# Sheet1.net
KiCad netlist of a schematic drawn in Altium Designer
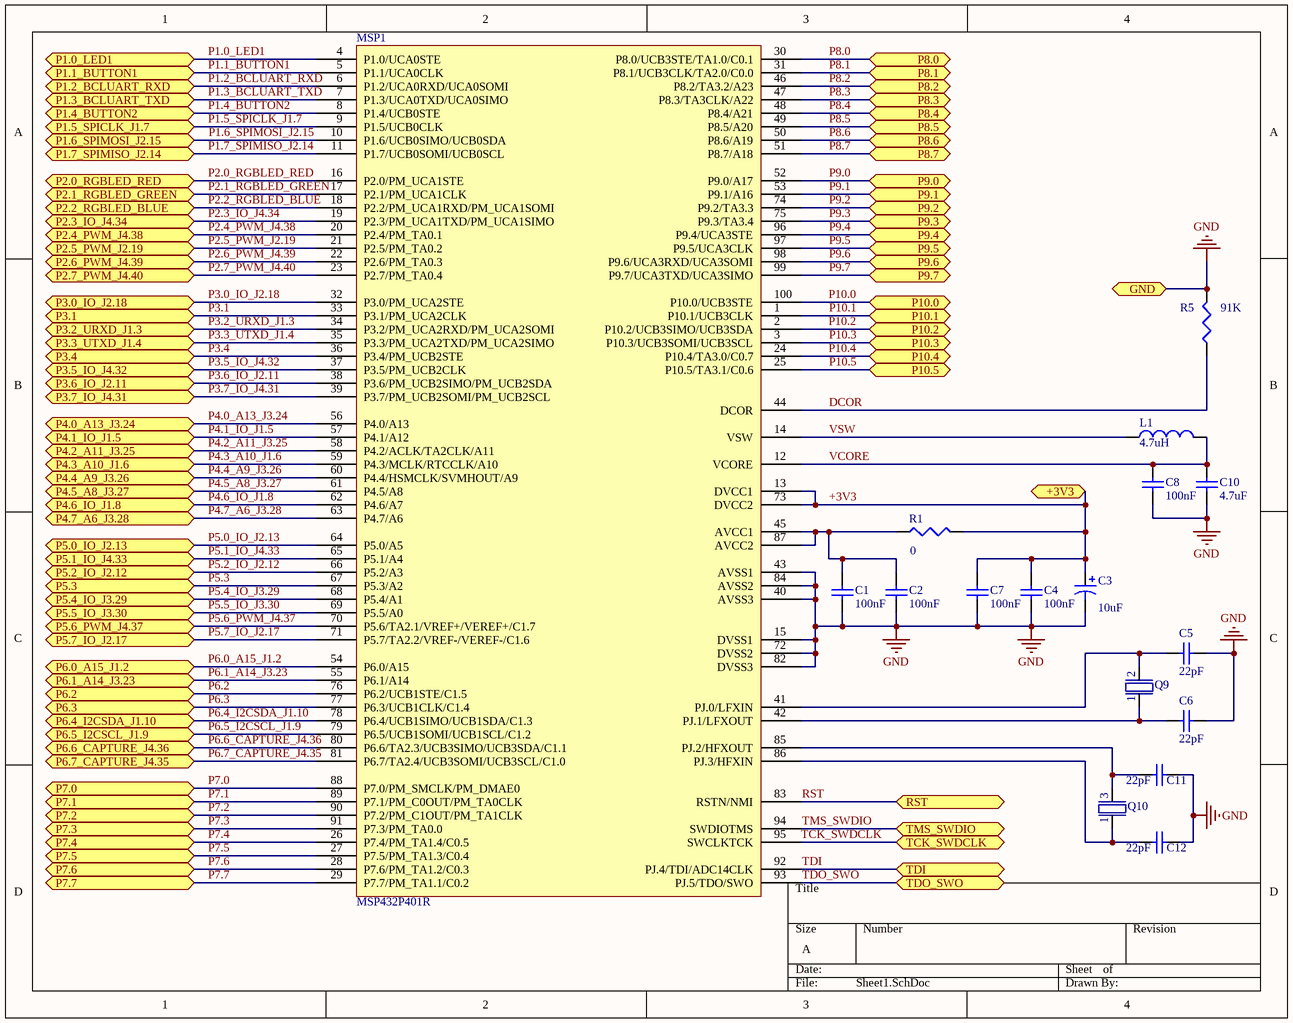
[diagram p0: Sheet1.SchDoc]

(export (version "E")
  (design (tool "Eeschema 10.0.6"))
  (components
    (comp (ref "C1")
      (value "100nF")
      (footprint "0402")
      (description "Capacitor (Semiconductor SIM Model)")
      (fields (field (name "Comment") "Cap Semi") (field (name "PUBLISHER") "Altium Limited"))
      (libsource (lib "Miscellaneous Devices") (part "Cap Semi"))
    )
    (comp (ref "C2")
      (value "100nF")
      (footprint "0402")
      (description "Capacitor (Semiconductor SIM Model)")
      (fields (field (name "Comment") "Cap Semi") (field (name "PUBLISHER") "Altium Limited"))
      (libsource (lib "Miscellaneous Devices") (part "Cap Semi"))
    )
    (comp (ref "C3")
      (value "10uF")
      (footprint "C0805")
      (description "Polarized Capacitor (Surface Mount)")
      (fields (field (name "Comment") "Cap Pol3") (field (name "PUBLISHER") "Altium Limited"))
      (libsource (lib "Miscellaneous Devices") (part "Cap Pol3"))
    )
    (comp (ref "C4")
      (value "100nF")
      (footprint "0402")
      (description "Capacitor (Semiconductor SIM Model)")
      (fields (field (name "Comment") "Cap Semi") (field (name "PUBLISHER") "Altium Limited"))
      (libsource (lib "Miscellaneous Devices") (part "Cap Semi"))
    )
    (comp (ref "C5")
      (value "22pF")
      (footprint "0402")
      (description "Capacitor (Semiconductor SIM Model)")
      (fields (field (name "Comment") "Cap Semi") (field (name "PUBLISHER") "Altium Limited"))
      (libsource (lib "Miscellaneous Devices") (part "Cap Semi"))
    )
    (comp (ref "C6")
      (value "22pF")
      (footprint "0402")
      (description "Capacitor (Semiconductor SIM Model)")
      (fields (field (name "Comment") "Cap Semi") (field (name "PUBLISHER") "Altium Limited"))
      (libsource (lib "Miscellaneous Devices") (part "Cap Semi"))
    )
    (comp (ref "C7")
      (value "100nF")
      (footprint "0402")
      (description "Capacitor (Semiconductor SIM Model)")
      (fields (field (name "Comment") "Cap Semi") (field (name "PUBLISHER") "Altium Limited"))
      (libsource (lib "Miscellaneous Devices") (part "Cap Semi"))
    )
    (comp (ref "C8")
      (value "100nF")
      (footprint "0402")
      (description "Capacitor (Semiconductor SIM Model)")
      (fields (field (name "Comment") "Cap Semi") (field (name "PUBLISHER") "Altium Limited"))
      (libsource (lib "Miscellaneous Devices") (part "Cap Semi"))
    )
    (comp (ref "C10")
      (value "4.7uF")
      (footprint "0402")
      (description "Capacitor (Semiconductor SIM Model)")
      (fields (field (name "Comment") "Cap Semi") (field (name "PUBLISHER") "Altium Limited"))
      (libsource (lib "Miscellaneous Devices") (part "Cap Semi"))
    )
    (comp (ref "C11")
      (value "22pF")
      (footprint "0402")
      (description "Capacitor (Semiconductor SIM Model)")
      (fields (field (name "Comment") "Cap Semi") (field (name "PUBLISHER") "Altium Limited"))
      (libsource (lib "Miscellaneous Devices") (part "Cap Semi"))
    )
    (comp (ref "C12")
      (value "22pF")
      (footprint "0402")
      (description "Capacitor (Semiconductor SIM Model)")
      (fields (field (name "Comment") "Cap Semi") (field (name "PUBLISHER") "Altium Limited"))
      (libsource (lib "Miscellaneous Devices") (part "Cap Semi"))
    )
    (comp (ref "L1")
      (value "4.7uH")
      (footprint "0402-A")
      (description "Inductor")
      (fields (field (name "PUBLISHER") "Altium Limited"))
      (libsource (lib "Miscellaneous Devices") (part "Inductor"))
    )
    (comp (ref "MSP1")
      (value "MSP432P401R")
      (footprint "MSP432P401R")
      (libsource (lib "actuatorBoard") (part "MSP432P401R"))
    )
    (comp (ref "Q9")
      (value "Crystal Oscillator")
      (fields (field (name "PIN1") "1") (field (name "PIN2") "2"))
      (libsource (lib "actuatorBoard") (part "Crystal Oscillator"))
    )
    (comp (ref "Q10")
      (value "Crystal Oscillator")
      (fields (field (name "PIN1") "1") (field (name "PIN2") "3"))
      (libsource (lib "actuatorBoard") (part "Crystal Oscillator"))
    )
    (comp (ref "R1")
      (value "0")
      (footprint "J1-0603")
      (description "Resistor")
      (fields (field (name "Comment") "Res3") (field (name "PUBLISHER") "Altium Limited"))
      (libsource (lib "Miscellaneous Devices") (part "Res3"))
    )
    (comp (ref "R5")
      (value "91K")
      (footprint "J1-0603")
      (description "Resistor")
      (fields (field (name "Comment") "Res3") (field (name "PUBLISHER") "Altium Limited"))
      (libsource (lib "Miscellaneous Devices") (part "Res3"))
    )
  )
  (nets
    (net (code "1") (name "/+3V3") (class "Default")
      (node (ref "C3") (pin "1") (pinfunction "1_1") (pintype "passive"))
      (node (ref "C4") (pin "2") (pinfunction "2_2") (pintype "passive"))
      (node (ref "C7") (pin "2") (pinfunction "2_2") (pintype "passive"))
      (node (ref "MSP1") (pin "13") (pinfunction "DVCC1_13") (pintype "passive"))
      (node (ref "MSP1") (pin "73") (pinfunction "DVCC2_73") (pintype "passive"))
      (node (ref "R1") (pin "2") (pinfunction "2_2") (pintype "passive"))
    )
    (net (code "2") (name "/DCOR") (class "Default")
      (node (ref "MSP1") (pin "44") (pinfunction "DCOR_44") (pintype "passive"))
      (node (ref "R5") (pin "1") (pinfunction "1_1") (pintype "passive"))
    )
    (net (code "3") (name "/P1.0_LED1") (class "Default")
      (node (ref "MSP1") (pin "4") (pinfunction "P1.0/UCA0STE_4") (pintype "passive"))
    )
    (net (code "4") (name "/P1.1_BUTTON1") (class "Default")
      (node (ref "MSP1") (pin "5") (pinfunction "P1.1/UCA0CLK_5") (pintype "passive"))
    )
    (net (code "5") (name "/P1.2_BCLUART_RXD") (class "Default")
      (node (ref "MSP1") (pin "6") (pinfunction "P1.2/UCA0RXD/UCA0SOMI_6") (pintype "passive"))
    )
    (net (code "6") (name "/P1.3_BCLUART_TXD") (class "Default")
      (node (ref "MSP1") (pin "7") (pinfunction "P1.3/UCA0TXD/UCA0SIMO_7") (pintype "passive"))
    )
    (net (code "7") (name "/P1.4_BUTTON2") (class "Default")
      (node (ref "MSP1") (pin "8") (pinfunction "P1.4/UCB0STE_8") (pintype "passive"))
    )
    (net (code "8") (name "/P1.5_SPICLK_J1.7") (class "Default")
      (node (ref "MSP1") (pin "9") (pinfunction "P1.5/UCB0CLK_9") (pintype "passive"))
    )
    (net (code "9") (name "/P1.6_SPIMOSI_J2.15") (class "Default")
      (node (ref "MSP1") (pin "10") (pinfunction "P1.6/UCB0SIMO/UCB0SDA_10") (pintype "passive"))
    )
    (net (code "10") (name "/P1.7_SPIMISO_J2.14") (class "Default")
      (node (ref "MSP1") (pin "11") (pinfunction "P1.7/UCB0SOMI/UCB0SCL_11") (pintype "passive"))
    )
    (net (code "11") (name "/P2.0_RGBLED_RED") (class "Default")
      (node (ref "MSP1") (pin "16") (pinfunction "P2.0/PM_UCA1STE_16") (pintype "passive"))
    )
    (net (code "12") (name "/P2.1_RGBLED_GREEN") (class "Default")
      (node (ref "MSP1") (pin "17") (pinfunction "P2.1/PM_UCA1CLK_17") (pintype "passive"))
    )
    (net (code "13") (name "/P2.2_RGBLED_BLUE") (class "Default")
      (node (ref "MSP1") (pin "18") (pinfunction "P2.2/PM_UCA1RXD/PM_UCA1SOMI_18") (pintype "passive"))
    )
    (net (code "14") (name "/P2.3_IO_J4.34") (class "Default")
      (node (ref "MSP1") (pin "19") (pinfunction "P2.3/PM_UCA1TXD/PM_UCA1SIMO_19") (pintype "passive"))
    )
    (net (code "15") (name "/P2.4_PWM_J4.38") (class "Default")
      (node (ref "MSP1") (pin "20") (pinfunction "P2.4/PM_TA0.1_20") (pintype "passive"))
    )
    (net (code "16") (name "/P2.5_PWM_J2.19") (class "Default")
      (node (ref "MSP1") (pin "21") (pinfunction "P2.5/PM_TA0.2_21") (pintype "passive"))
    )
    (net (code "17") (name "/P2.6_PWM_J4.39") (class "Default")
      (node (ref "MSP1") (pin "22") (pinfunction "P2.6/PM_TA0.3_22") (pintype "passive"))
    )
    (net (code "18") (name "/P2.7_PWM_J4.40") (class "Default")
      (node (ref "MSP1") (pin "23") (pinfunction "P2.7/PM_TA0.4_23") (pintype "passive"))
    )
    (net (code "19") (name "/P3.0_IO_J2.18") (class "Default")
      (node (ref "MSP1") (pin "32") (pinfunction "P3.0/PM_UCA2STE_32") (pintype "passive"))
    )
    (net (code "20") (name "/P3.1") (class "Default")
      (node (ref "MSP1") (pin "33") (pinfunction "P3.1/PM_UCA2CLK_33") (pintype "passive"))
    )
    (net (code "21") (name "/P3.2_URXD_J1.3") (class "Default")
      (node (ref "MSP1") (pin "34") (pinfunction "P3.2/PM_UCA2RXD/PM_UCA2SOMI_34") (pintype "passive"))
    )
    (net (code "22") (name "/P3.3_UTXD_J1.4") (class "Default")
      (node (ref "MSP1") (pin "35") (pinfunction "P3.3/PM_UCA2TXD/PM_UCA2SIMO_35") (pintype "passive"))
    )
    (net (code "23") (name "/P3.4") (class "Default")
      (node (ref "MSP1") (pin "36") (pinfunction "P3.4/PM_UCB2STE_36") (pintype "passive"))
    )
    (net (code "24") (name "/P3.5_IO_J4.32") (class "Default")
      (node (ref "MSP1") (pin "37") (pinfunction "P3.5/PM_UCB2CLK_37") (pintype "passive"))
    )
    (net (code "25") (name "/P3.6_IO_J2.11") (class "Default")
      (node (ref "MSP1") (pin "38") (pinfunction "P3.6/PM_UCB2SIMO/PM_UCB2SDA_38") (pintype "passive"))
    )
    (net (code "26") (name "/P3.7_IO_J4.31") (class "Default")
      (node (ref "MSP1") (pin "39") (pinfunction "P3.7/PM_UCB2SOMI/PM_UCB2SCL_39") (pintype "passive"))
    )
    (net (code "27") (name "/P4.0_A13_J3.24") (class "Default")
      (node (ref "MSP1") (pin "56") (pinfunction "P4.0/A13_56") (pintype "passive"))
    )
    (net (code "28") (name "/P4.1_IO_J1.5") (class "Default")
      (node (ref "MSP1") (pin "57") (pinfunction "P4.1/A12_57") (pintype "passive"))
    )
    (net (code "29") (name "/P4.2_A11_J3.25") (class "Default")
      (node (ref "MSP1") (pin "58") (pinfunction "P4.2/ACLK/TA2CLK/A11_58") (pintype "passive"))
    )
    (net (code "30") (name "/P4.3_A10_J1.6") (class "Default")
      (node (ref "MSP1") (pin "59") (pinfunction "P4.3/MCLK/RTCCLK/A10_59") (pintype "passive"))
    )
    (net (code "31") (name "/P4.4_A9_J3.26") (class "Default")
      (node (ref "MSP1") (pin "60") (pinfunction "P4.4/HSMCLK/SVMHOUT/A9_60") (pintype "passive"))
    )
    (net (code "32") (name "/P4.5_A8_J3.27") (class "Default")
      (node (ref "MSP1") (pin "61") (pinfunction "P4.5/A8_61") (pintype "passive"))
    )
    (net (code "33") (name "/P4.6_IO_J1.8") (class "Default")
      (node (ref "MSP1") (pin "62") (pinfunction "P4.6/A7_62") (pintype "passive"))
    )
    (net (code "34") (name "/P4.7_A6_J3.28") (class "Default")
      (node (ref "MSP1") (pin "63") (pinfunction "P4.7/A6_63") (pintype "passive"))
    )
    (net (code "35") (name "/P5.0_IO_J2.13") (class "Default")
      (node (ref "MSP1") (pin "64") (pinfunction "P5.0/A5_64") (pintype "passive"))
    )
    (net (code "36") (name "/P5.1_IO_J4.33") (class "Default")
      (node (ref "MSP1") (pin "65") (pinfunction "P5.1/A4_65") (pintype "passive"))
    )
    (net (code "37") (name "/P5.2_IO_J2.12") (class "Default")
      (node (ref "MSP1") (pin "66") (pinfunction "P5.2/A3_66") (pintype "passive"))
    )
    (net (code "38") (name "/P5.3") (class "Default")
      (node (ref "MSP1") (pin "67") (pinfunction "P5.3/A2_67") (pintype "passive"))
    )
    (net (code "39") (name "/P5.4_IO_J3.29") (class "Default")
      (node (ref "MSP1") (pin "68") (pinfunction "P5.4/A1_68") (pintype "passive"))
    )
    (net (code "40") (name "/P5.5_IO_J3.30") (class "Default")
      (node (ref "MSP1") (pin "69") (pinfunction "P5.5/A0_69") (pintype "passive"))
    )
    (net (code "41") (name "/P5.6_PWM_J4.37") (class "Default")
      (node (ref "MSP1") (pin "70") (pinfunction "P5.6/TA2.1/VREF+/VEREF+/C1.7_70") (pintype "passive"))
    )
    (net (code "42") (name "/P5.7_IO_J2.17") (class "Default")
      (node (ref "MSP1") (pin "71") (pinfunction "P5.7/TA2.2/VREF-/VEREF-/C1.6_71") (pintype "passive"))
    )
    (net (code "43") (name "/P6.0_A15_J1.2") (class "Default")
      (node (ref "MSP1") (pin "54") (pinfunction "P6.0/A15_54") (pintype "passive"))
    )
    (net (code "44") (name "/P6.1_A14_J3.23") (class "Default")
      (node (ref "MSP1") (pin "55") (pinfunction "P6.1/A14_55") (pintype "passive"))
    )
    (net (code "45") (name "/P6.2") (class "Default")
      (node (ref "MSP1") (pin "76") (pinfunction "P6.2/UCB1STE/C1.5_76") (pintype "passive"))
    )
    (net (code "46") (name "/P6.3") (class "Default")
      (node (ref "MSP1") (pin "77") (pinfunction "P6.3/UCB1CLK/C1.4_77") (pintype "passive"))
    )
    (net (code "47") (name "/P6.4_I2CSDA_J1.10") (class "Default")
      (node (ref "MSP1") (pin "78") (pinfunction "P6.4/UCB1SIMO/UCB1SDA/C1.3_78") (pintype "passive"))
    )
    (net (code "48") (name "/P6.5_I2CSCL_J1.9") (class "Default")
      (node (ref "MSP1") (pin "79") (pinfunction "P6.5/UCB1SOMI/UCB1SCL/C1.2_79") (pintype "passive"))
    )
    (net (code "49") (name "/P6.6_CAPTURE_J4.36") (class "Default")
      (node (ref "MSP1") (pin "80") (pinfunction "P6.6/TA2.3/UCB3SIMO/UCB3SDA/C1.1_80") (pintype "passive"))
    )
    (net (code "50") (name "/P6.7_CAPTURE_J4.35") (class "Default")
      (node (ref "MSP1") (pin "81") (pinfunction "P6.7/TA2.4/UCB3SOMI/UCB3SCL/C1.0_81") (pintype "passive"))
    )
    (net (code "51") (name "/P7.0") (class "Default")
      (node (ref "MSP1") (pin "88") (pinfunction "P7.0/PM_SMCLK/PM_DMAE0_88") (pintype "passive"))
    )
    (net (code "52") (name "/P7.1") (class "Default")
      (node (ref "MSP1") (pin "89") (pinfunction "P7.1/PM_C0OUT/PM_TA0CLK_89") (pintype "passive"))
    )
    (net (code "53") (name "/P7.2") (class "Default")
      (node (ref "MSP1") (pin "90") (pinfunction "P7.2/PM_C1OUT/PM_TA1CLK_90") (pintype "passive"))
    )
    (net (code "54") (name "/P7.3") (class "Default")
      (node (ref "MSP1") (pin "91") (pinfunction "P7.3/PM_TA0.0_91") (pintype "passive"))
    )
    (net (code "55") (name "/P7.4") (class "Default")
      (node (ref "MSP1") (pin "26") (pinfunction "P7.4/PM_TA1.4/C0.5_26") (pintype "passive"))
    )
    (net (code "56") (name "/P7.5") (class "Default")
      (node (ref "MSP1") (pin "27") (pinfunction "P7.5/PM_TA1.3/C0.4_27") (pintype "passive"))
    )
    (net (code "57") (name "/P7.6") (class "Default")
      (node (ref "MSP1") (pin "28") (pinfunction "P7.6/PM_TA1.2/C0.3_28") (pintype "passive"))
    )
    (net (code "58") (name "/P7.7") (class "Default")
      (node (ref "MSP1") (pin "29") (pinfunction "P7.7/PM_TA1.1/C0.2_29") (pintype "passive"))
    )
    (net (code "59") (name "/P8.0") (class "Default")
      (node (ref "MSP1") (pin "30") (pinfunction "P8.0/UCB3STE/TA1.0/C0.1_30") (pintype "passive"))
    )
    (net (code "60") (name "/P8.1") (class "Default")
      (node (ref "MSP1") (pin "31") (pinfunction "P8.1/UCB3CLK/TA2.0/C0.0_31") (pintype "passive"))
    )
    (net (code "61") (name "/P8.2") (class "Default")
      (node (ref "MSP1") (pin "46") (pinfunction "P8.2/TA3.2/A23_46") (pintype "passive"))
    )
    (net (code "62") (name "/P8.3") (class "Default")
      (node (ref "MSP1") (pin "47") (pinfunction "P8.3/TA3CLK/A22_47") (pintype "passive"))
    )
    (net (code "63") (name "/P8.4") (class "Default")
      (node (ref "MSP1") (pin "48") (pinfunction "P8.4/A21_48") (pintype "passive"))
    )
    (net (code "64") (name "/P8.5") (class "Default")
      (node (ref "MSP1") (pin "49") (pinfunction "P8.5/A20_49") (pintype "passive"))
    )
    (net (code "65") (name "/P8.6") (class "Default")
      (node (ref "MSP1") (pin "50") (pinfunction "P8.6/A19_50") (pintype "passive"))
    )
    (net (code "66") (name "/P8.7") (class "Default")
      (node (ref "MSP1") (pin "51") (pinfunction "P8.7/A18_51") (pintype "passive"))
    )
    (net (code "67") (name "/P9.0") (class "Default")
      (node (ref "MSP1") (pin "52") (pinfunction "P9.0/A17_52") (pintype "passive"))
    )
    (net (code "68") (name "/P9.1") (class "Default")
      (node (ref "MSP1") (pin "53") (pinfunction "P9.1/A16_53") (pintype "passive"))
    )
    (net (code "69") (name "/P9.2") (class "Default")
      (node (ref "MSP1") (pin "74") (pinfunction "P9.2/TA3.3_74") (pintype "passive"))
    )
    (net (code "70") (name "/P9.3") (class "Default")
      (node (ref "MSP1") (pin "75") (pinfunction "P9.3/TA3.4_75") (pintype "passive"))
    )
    (net (code "71") (name "/P9.4") (class "Default")
      (node (ref "MSP1") (pin "96") (pinfunction "P9.4/UCA3STE_96") (pintype "passive"))
    )
    (net (code "72") (name "/P9.5") (class "Default")
      (node (ref "MSP1") (pin "97") (pinfunction "P9.5/UCA3CLK_97") (pintype "passive"))
    )
    (net (code "73") (name "/P9.6") (class "Default")
      (node (ref "MSP1") (pin "98") (pinfunction "P9.6/UCA3RXD/UCA3SOMI_98") (pintype "passive"))
    )
    (net (code "74") (name "/P9.7") (class "Default")
      (node (ref "MSP1") (pin "99") (pinfunction "P9.7/UCA3TXD/UCA3SIMO_99") (pintype "passive"))
    )
    (net (code "75") (name "/P10.0") (class "Default")
      (node (ref "MSP1") (pin "100") (pinfunction "P10.0/UCB3STE_100") (pintype "passive"))
    )
    (net (code "76") (name "/P10.1") (class "Default")
      (node (ref "MSP1") (pin "1") (pinfunction "P10.1/UCB3CLK_1") (pintype "passive"))
    )
    (net (code "77") (name "/P10.2") (class "Default")
      (node (ref "MSP1") (pin "2") (pinfunction "P10.2/UCB3SIMO/UCB3SDA_2") (pintype "passive"))
    )
    (net (code "78") (name "/P10.3") (class "Default")
      (node (ref "MSP1") (pin "3") (pinfunction "P10.3/UCB3SOMI/UCB3SCL_3") (pintype "passive"))
    )
    (net (code "79") (name "/P10.4") (class "Default")
      (node (ref "MSP1") (pin "24") (pinfunction "P10.4/TA3.0/C0.7_24") (pintype "passive"))
    )
    (net (code "80") (name "/P10.5") (class "Default")
      (node (ref "MSP1") (pin "25") (pinfunction "P10.5/TA3.1/C0.6_25") (pintype "passive"))
    )
    (net (code "81") (name "/RST") (class "Default")
      (node (ref "MSP1") (pin "83") (pinfunction "RSTN/NMI_83") (pintype "passive"))
    )
    (net (code "82") (name "/TCK_SWDCLK") (class "Default")
      (node (ref "MSP1") (pin "95") (pinfunction "SWCLKTCK_95") (pintype "passive"))
    )
    (net (code "83") (name "/TDI") (class "Default")
      (node (ref "MSP1") (pin "92") (pinfunction "PJ.4/TDI/ADC14CLK_92") (pintype "passive"))
    )
    (net (code "84") (name "/TDO_SWO") (class "Default")
      (node (ref "MSP1") (pin "93") (pinfunction "PJ.5/TDO/SWO_93") (pintype "passive"))
    )
    (net (code "85") (name "/TMS_SWDIO") (class "Default")
      (node (ref "MSP1") (pin "94") (pinfunction "SWDIOTMS_94") (pintype "passive"))
    )
    (net (code "86") (name "/VCORE") (class "Default")
      (node (ref "C10") (pin "2") (pinfunction "2_2") (pintype "passive"))
      (node (ref "C8") (pin "2") (pinfunction "2_2") (pintype "passive"))
      (node (ref "L1") (pin "2") (pinfunction "2_2") (pintype "passive"))
      (node (ref "MSP1") (pin "12") (pinfunction "VCORE_12") (pintype "passive"))
    )
    (net (code "87") (name "/VSW") (class "Default")
      (node (ref "L1") (pin "1") (pinfunction "1_1") (pintype "passive"))
      (node (ref "MSP1") (pin "14") (pinfunction "VSW_14") (pintype "passive"))
    )
    (net (code "88") (name "GND") (class "Default")
      (node (ref "C1") (pin "1") (pinfunction "1_1") (pintype "passive"))
      (node (ref "C10") (pin "1") (pinfunction "1_1") (pintype "passive"))
      (node (ref "C11") (pin "1") (pinfunction "1_1") (pintype "passive"))
      (node (ref "C12") (pin "1") (pinfunction "1_1") (pintype "passive"))
      (node (ref "C2") (pin "1") (pinfunction "1_1") (pintype "passive"))
      (node (ref "C3") (pin "2") (pinfunction "2_2") (pintype "passive"))
      (node (ref "C4") (pin "1") (pinfunction "1_1") (pintype "passive"))
      (node (ref "C5") (pin "1") (pinfunction "1_1") (pintype "passive"))
      (node (ref "C6") (pin "1") (pinfunction "1_1") (pintype "passive"))
      (node (ref "C7") (pin "1") (pinfunction "1_1") (pintype "passive"))
      (node (ref "C8") (pin "1") (pinfunction "1_1") (pintype "passive"))
      (node (ref "MSP1") (pin "15") (pinfunction "DVSS1_15") (pintype "passive"))
      (node (ref "MSP1") (pin "40") (pinfunction "AVSS3_40") (pintype "passive"))
      (node (ref "MSP1") (pin "43") (pinfunction "AVSS1_43") (pintype "passive"))
      (node (ref "MSP1") (pin "72") (pinfunction "DVSS2_72") (pintype "passive"))
      (node (ref "MSP1") (pin "82") (pinfunction "DVSS3_82") (pintype "passive"))
      (node (ref "MSP1") (pin "84") (pinfunction "AVSS2_84") (pintype "passive"))
      (node (ref "R5") (pin "2") (pinfunction "2_2") (pintype "passive"))
    )
    (net (code "89") (name "Net-(MSP1-AVCC1)") (class "Default")
      (node (ref "C1") (pin "2") (pinfunction "2_2") (pintype "passive"))
      (node (ref "C2") (pin "2") (pinfunction "2_2") (pintype "passive"))
      (node (ref "MSP1") (pin "45") (pinfunction "AVCC1_45") (pintype "passive"))
      (node (ref "MSP1") (pin "87") (pinfunction "AVCC2_87") (pintype "passive"))
      (node (ref "R1") (pin "1") (pinfunction "1_1") (pintype "passive"))
    )
    (net (code "90") (name "Net-(MSP1-PJ.0{slash}LFXIN)") (class "Default")
      (node (ref "C5") (pin "2") (pinfunction "2_2") (pintype "passive"))
      (node (ref "MSP1") (pin "41") (pinfunction "PJ.0/LFXIN_41") (pintype "passive"))
      (node (ref "Q9") (pin "2") (pinfunction "2_2") (pintype "passive"))
    )
    (net (code "91") (name "Net-(MSP1-PJ.1{slash}LFXOUT)") (class "Default")
      (node (ref "C6") (pin "2") (pinfunction "2_2") (pintype "passive"))
      (node (ref "MSP1") (pin "42") (pinfunction "PJ.1/LFXOUT_42") (pintype "passive"))
      (node (ref "Q9") (pin "1") (pinfunction "1_1") (pintype "passive"))
    )
    (net (code "92") (name "Net-(MSP1-PJ.2{slash}HFXOUT)") (class "Default")
      (node (ref "C11") (pin "2") (pinfunction "2_2") (pintype "passive"))
      (node (ref "MSP1") (pin "85") (pinfunction "PJ.2/HFXOUT_85") (pintype "passive"))
      (node (ref "Q10") (pin "2") (pinfunction "2_2") (pintype "passive"))
    )
    (net (code "93") (name "Net-(MSP1-PJ.3{slash}HFXIN)") (class "Default")
      (node (ref "C12") (pin "2") (pinfunction "2_2") (pintype "passive"))
      (node (ref "MSP1") (pin "86") (pinfunction "PJ.3/HFXIN_86") (pintype "passive"))
      (node (ref "Q10") (pin "1") (pinfunction "1_1") (pintype "passive"))
    )
  )
)
